# ControlBoard-v1_0.net
KiCad netlist of a schematic drawn in EAGLE
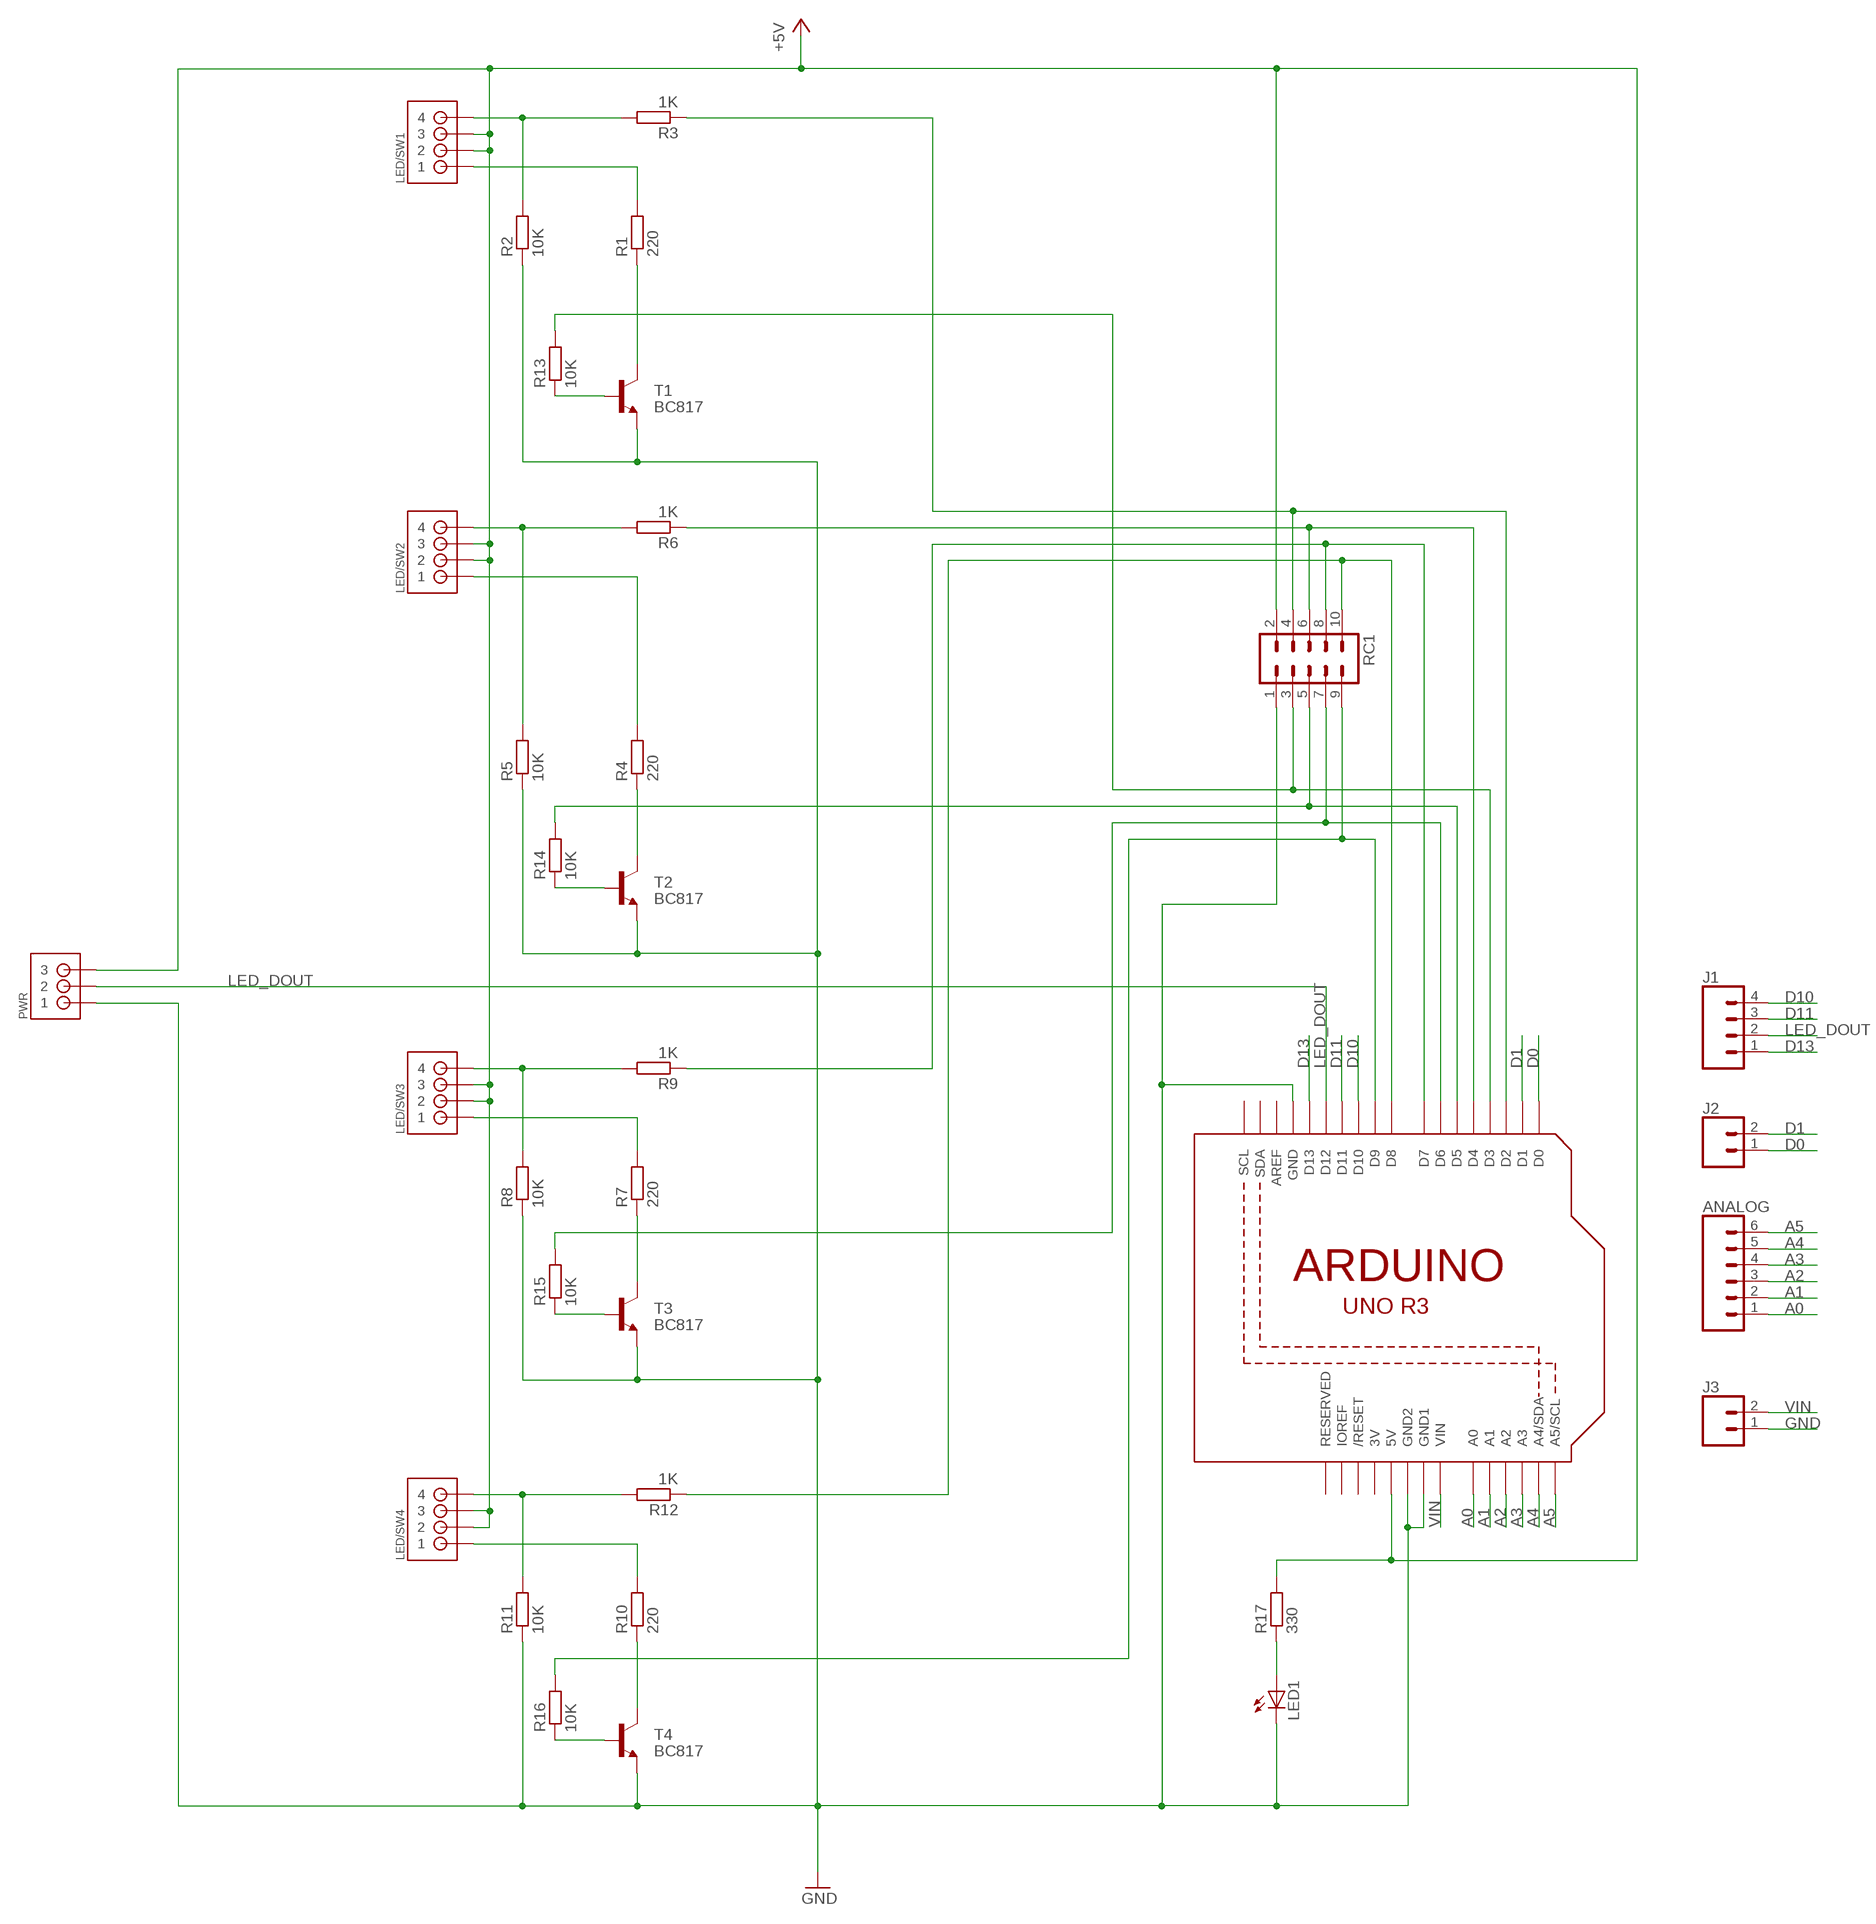
[diagram p0: schematic, sheet 1]

(export (version "E")
  (design (tool "Eeschema 10.0.6"))
  (components
    (comp (ref "ANALOG")
      (value "CONN_06SILK_FEMALE_PTH")
      (footprint "eagle-import:1X06")
      (libsource (lib "eagle-import") (part "CONN_06SILK_FEMALE_PTH"))
    )
    (comp (ref "J1")
      (value "CONN_04")
      (footprint "eagle-import:1X04")
      (libsource (lib "eagle-import") (part "CONN_04"))
    )
    (comp (ref "J2")
      (value "CONN_02")
      (footprint "eagle-import:1X02")
      (libsource (lib "eagle-import") (part "CONN_02"))
    )
    (comp (ref "J3")
      (value "CONN_02")
      (footprint "eagle-import:1X02")
      (libsource (lib "eagle-import") (part "CONN_02"))
    )
    (comp (ref "LED/SW1")
      (value "JST-XA-04-PIN")
      (footprint "eagle-import:JST-XA-04")
      (libsource (lib "eagle-import") (part "JST-XA-04-PIN"))
    )
    (comp (ref "LED/SW2")
      (value "JST-XA-04-PIN")
      (footprint "eagle-import:JST-XA-04")
      (libsource (lib "eagle-import") (part "JST-XA-04-PIN"))
    )
    (comp (ref "LED/SW3")
      (value "JST-XA-04-PIN")
      (footprint "eagle-import:JST-XA-04")
      (libsource (lib "eagle-import") (part "JST-XA-04-PIN"))
    )
    (comp (ref "LED/SW4")
      (value "JST-XA-04-PIN")
      (footprint "eagle-import:JST-XA-04")
      (libsource (lib "eagle-import") (part "JST-XA-04-PIN"))
    )
    (comp (ref "LED1")
      (value "LEDCHIPLED_0805")
      (footprint "eagle-import:CHIPLED_0805")
      (libsource (lib "eagle-import") (part "LEDCHIPLED_0805"))
    )
    (comp (ref "PWR")
      (value "JST-XA-03-PIN")
      (footprint "eagle-import:JST-XA-03")
      (libsource (lib "eagle-import") (part "JST-XA-03-PIN"))
    )
    (comp (ref "R1")
      (value "220")
      (footprint "eagle-import:R0805")
      (libsource (lib "eagle-import") (part "RESISTORR0805"))
    )
    (comp (ref "R2")
      (value "10K")
      (footprint "eagle-import:R0805")
      (libsource (lib "eagle-import") (part "RESISTORR0805"))
    )
    (comp (ref "R3")
      (value "1K")
      (footprint "eagle-import:R0805")
      (libsource (lib "eagle-import") (part "RESISTORR0805"))
    )
    (comp (ref "R4")
      (value "220")
      (footprint "eagle-import:R0805")
      (libsource (lib "eagle-import") (part "RESISTORR0805"))
    )
    (comp (ref "R5")
      (value "10K")
      (footprint "eagle-import:R0805")
      (libsource (lib "eagle-import") (part "RESISTORR0805"))
    )
    (comp (ref "R6")
      (value "1K")
      (footprint "eagle-import:R0805")
      (libsource (lib "eagle-import") (part "RESISTORR0805"))
    )
    (comp (ref "R7")
      (value "220")
      (footprint "eagle-import:R0805")
      (libsource (lib "eagle-import") (part "RESISTORR0805"))
    )
    (comp (ref "R8")
      (value "10K")
      (footprint "eagle-import:R0805")
      (libsource (lib "eagle-import") (part "RESISTORR0805"))
    )
    (comp (ref "R9")
      (value "1K")
      (footprint "eagle-import:R0805")
      (libsource (lib "eagle-import") (part "RESISTORR0805"))
    )
    (comp (ref "R10")
      (value "220")
      (footprint "eagle-import:R0805")
      (libsource (lib "eagle-import") (part "RESISTORR0805"))
    )
    (comp (ref "R11")
      (value "10K")
      (footprint "eagle-import:R0805")
      (libsource (lib "eagle-import") (part "RESISTORR0805"))
    )
    (comp (ref "R12")
      (value "1K")
      (footprint "eagle-import:R0805")
      (libsource (lib "eagle-import") (part "RESISTORR0805"))
    )
    (comp (ref "R13")
      (value "10K")
      (footprint "eagle-import:R0805")
      (libsource (lib "eagle-import") (part "RESISTORR0805"))
    )
    (comp (ref "R14")
      (value "10K")
      (footprint "eagle-import:R0805")
      (libsource (lib "eagle-import") (part "RESISTORR0805"))
    )
    (comp (ref "R15")
      (value "10K")
      (footprint "eagle-import:R0805")
      (libsource (lib "eagle-import") (part "RESISTORR0805"))
    )
    (comp (ref "R16")
      (value "10K")
      (footprint "eagle-import:R0805")
      (libsource (lib "eagle-import") (part "RESISTORR0805"))
    )
    (comp (ref "R17")
      (value "330")
      (footprint "eagle-import:R0805")
      (libsource (lib "eagle-import") (part "RESISTORR0805"))
    )
    (comp (ref "RC1")
      (value "ML10")
      (footprint "eagle-import:ML10")
      (libsource (lib "eagle-import") (part "ML10"))
    )
    (comp (ref "T1")
      (value "BC817")
      (footprint "eagle-import:SOT23")
      (libsource (lib "eagle-import") (part "BC817"))
    )
    (comp (ref "T2")
      (value "BC817")
      (footprint "eagle-import:SOT23")
      (libsource (lib "eagle-import") (part "BC817"))
    )
    (comp (ref "T3")
      (value "BC817")
      (footprint "eagle-import:SOT23")
      (libsource (lib "eagle-import") (part "BC817"))
    )
    (comp (ref "T4")
      (value "BC817")
      (footprint "eagle-import:SOT23")
      (libsource (lib "eagle-import") (part "BC817"))
    )
    (comp (ref "U1")
      (value "ARDUINO-SHIELDLET")
      (footprint "eagle-import:ARDUINOR3-PINS")
      (libsource (lib "eagle-import") (part "ARDUINO-SHIELDLET"))
    )
  )
  (nets
    (net (code "1") (name "+5V") (class "Default")
      (node (ref "LED/SW1") (pin "2") (pinfunction "2_2") (pintype "bidirectional"))
      (node (ref "LED/SW1") (pin "3") (pinfunction "3_3") (pintype "bidirectional"))
      (node (ref "LED/SW2") (pin "2") (pinfunction "2_2") (pintype "bidirectional"))
      (node (ref "LED/SW2") (pin "3") (pinfunction "3_3") (pintype "bidirectional"))
      (node (ref "LED/SW3") (pin "2") (pinfunction "2_2") (pintype "bidirectional"))
      (node (ref "LED/SW3") (pin "3") (pinfunction "3_3") (pintype "bidirectional"))
      (node (ref "LED/SW4") (pin "2") (pinfunction "2_2") (pintype "bidirectional"))
      (node (ref "LED/SW4") (pin "3") (pinfunction "3_3") (pintype "bidirectional"))
      (node (ref "PWR") (pin "3") (pinfunction "3_3") (pintype "bidirectional"))
      (node (ref "R17") (pin "2") (pinfunction "2_2") (pintype "passive"))
      (node (ref "RC1") (pin "2") (pinfunction "2_2") (pintype "passive"))
      (node (ref "U1") (pin "5V") (pinfunction "5V_5V") (pintype "power_in"))
    )
    (net (code "2") (name "/3V") (class "Default")
      (node (ref "U1") (pin "3V") (pinfunction "3V_3V") (pintype "power_in"))
    )
    (net (code "3") (name "/A0") (class "Default")
      (node (ref "ANALOG") (pin "1") (pinfunction "1_1") (pintype "passive"))
      (node (ref "U1") (pin "A0") (pinfunction "A0_A0") (pintype "bidirectional"))
    )
    (net (code "4") (name "/A1") (class "Default")
      (node (ref "ANALOG") (pin "2") (pinfunction "2_2") (pintype "passive"))
      (node (ref "U1") (pin "A1") (pinfunction "A1_A1") (pintype "bidirectional"))
    )
    (net (code "5") (name "/A2") (class "Default")
      (node (ref "ANALOG") (pin "3") (pinfunction "3_3") (pintype "passive"))
      (node (ref "U1") (pin "A2") (pinfunction "A2_A2") (pintype "bidirectional"))
    )
    (net (code "6") (name "/A3") (class "Default")
      (node (ref "ANALOG") (pin "4") (pinfunction "4_4") (pintype "passive"))
      (node (ref "U1") (pin "A3") (pinfunction "A3_A3") (pintype "bidirectional"))
    )
    (net (code "7") (name "/A4") (class "Default")
      (node (ref "ANALOG") (pin "5") (pinfunction "5_5") (pintype "passive"))
      (node (ref "U1") (pin "A4") (pinfunction "A4/SDA_A4") (pintype "bidirectional"))
    )
    (net (code "8") (name "/A5") (class "Default")
      (node (ref "ANALOG") (pin "6") (pinfunction "6_6") (pintype "passive"))
      (node (ref "U1") (pin "A5") (pinfunction "A5/SCL_A5") (pintype "bidirectional"))
    )
    (net (code "9") (name "/D0") (class "Default")
      (node (ref "J2") (pin "1") (pinfunction "1_1") (pintype "passive"))
      (node (ref "U1") (pin "D0") (pinfunction "D0_D0") (pintype "bidirectional"))
    )
    (net (code "10") (name "/D1") (class "Default")
      (node (ref "J2") (pin "2") (pinfunction "2_2") (pintype "passive"))
      (node (ref "U1") (pin "D1") (pinfunction "D1_D1") (pintype "bidirectional"))
    )
    (net (code "11") (name "/D10") (class "Default")
      (node (ref "J1") (pin "4") (pinfunction "4_4") (pintype "passive"))
      (node (ref "U1") (pin "D10") (pinfunction "D10_D10") (pintype "bidirectional"))
    )
    (net (code "12") (name "/D11") (class "Default")
      (node (ref "J1") (pin "3") (pinfunction "3_3") (pintype "passive"))
      (node (ref "U1") (pin "D11") (pinfunction "D11_D11") (pintype "bidirectional"))
    )
    (net (code "13") (name "/D13") (class "Default")
      (node (ref "J1") (pin "1") (pinfunction "1_1") (pintype "passive"))
      (node (ref "U1") (pin "D13") (pinfunction "D13_D13") (pintype "bidirectional"))
    )
    (net (code "14") (name "/LED_DOUT") (class "Default")
      (node (ref "J1") (pin "2") (pinfunction "2_2") (pintype "passive"))
      (node (ref "PWR") (pin "2") (pinfunction "2_2") (pintype "bidirectional"))
      (node (ref "U1") (pin "D12") (pinfunction "D12_D12") (pintype "bidirectional"))
    )
    (net (code "15") (name "/VIN") (class "Default")
      (node (ref "J3") (pin "2") (pinfunction "2_2") (pintype "passive"))
      (node (ref "U1") (pin "VIN") (pinfunction "VIN_VIN") (pintype "power_in"))
    )
    (net (code "16") (name "GND") (class "Default")
      (node (ref "J3") (pin "1") (pinfunction "1_1") (pintype "passive"))
      (node (ref "LED1") (pin "C") (pinfunction "C_C") (pintype "passive"))
      (node (ref "PWR") (pin "1") (pinfunction "1_1") (pintype "bidirectional"))
      (node (ref "R11") (pin "1") (pinfunction "1_1") (pintype "passive"))
      (node (ref "R2") (pin "1") (pinfunction "1_1") (pintype "passive"))
      (node (ref "R5") (pin "1") (pinfunction "1_1") (pintype "passive"))
      (node (ref "R8") (pin "1") (pinfunction "1_1") (pintype "passive"))
      (node (ref "RC1") (pin "1") (pinfunction "1_1") (pintype "passive"))
      (node (ref "T1") (pin "2") (pinfunction "E_2") (pintype "passive"))
      (node (ref "T2") (pin "2") (pinfunction "E_2") (pintype "passive"))
      (node (ref "T3") (pin "2") (pinfunction "E_2") (pintype "passive"))
      (node (ref "T4") (pin "2") (pinfunction "E_2") (pintype "passive"))
      (node (ref "U1") (pin "GND") (pinfunction "GND_GND") (pintype "power_in"))
      (node (ref "U1") (pin "GND1") (pinfunction "GND1_GND1") (pintype "power_in"))
      (node (ref "U1") (pin "GND2") (pinfunction "GND2_GND2") (pintype "power_in"))
    )
    (net (code "17") (name "Net-(LED/SW1-Pad1)") (class "Default")
      (node (ref "LED/SW1") (pin "1") (pinfunction "1_1") (pintype "bidirectional"))
      (node (ref "R1") (pin "2") (pinfunction "2_2") (pintype "passive"))
    )
    (net (code "18") (name "Net-(LED/SW1-Pad4)") (class "Default")
      (node (ref "LED/SW1") (pin "4") (pinfunction "4_4") (pintype "bidirectional"))
      (node (ref "R2") (pin "2") (pinfunction "2_2") (pintype "passive"))
      (node (ref "R3") (pin "2") (pinfunction "2_2") (pintype "passive"))
    )
    (net (code "19") (name "Net-(LED/SW2-Pad1)") (class "Default")
      (node (ref "LED/SW2") (pin "1") (pinfunction "1_1") (pintype "bidirectional"))
      (node (ref "R4") (pin "2") (pinfunction "2_2") (pintype "passive"))
    )
    (net (code "20") (name "Net-(LED/SW2-Pad4)") (class "Default")
      (node (ref "LED/SW2") (pin "4") (pinfunction "4_4") (pintype "bidirectional"))
      (node (ref "R5") (pin "2") (pinfunction "2_2") (pintype "passive"))
      (node (ref "R6") (pin "2") (pinfunction "2_2") (pintype "passive"))
    )
    (net (code "21") (name "Net-(LED/SW3-Pad1)") (class "Default")
      (node (ref "LED/SW3") (pin "1") (pinfunction "1_1") (pintype "bidirectional"))
      (node (ref "R7") (pin "2") (pinfunction "2_2") (pintype "passive"))
    )
    (net (code "22") (name "Net-(LED/SW3-Pad4)") (class "Default")
      (node (ref "LED/SW3") (pin "4") (pinfunction "4_4") (pintype "bidirectional"))
      (node (ref "R8") (pin "2") (pinfunction "2_2") (pintype "passive"))
      (node (ref "R9") (pin "2") (pinfunction "2_2") (pintype "passive"))
    )
    (net (code "23") (name "Net-(LED/SW4-Pad1)") (class "Default")
      (node (ref "LED/SW4") (pin "1") (pinfunction "1_1") (pintype "bidirectional"))
      (node (ref "R10") (pin "2") (pinfunction "2_2") (pintype "passive"))
    )
    (net (code "24") (name "Net-(LED/SW4-Pad4)") (class "Default")
      (node (ref "LED/SW4") (pin "4") (pinfunction "4_4") (pintype "bidirectional"))
      (node (ref "R11") (pin "2") (pinfunction "2_2") (pintype "passive"))
      (node (ref "R12") (pin "2") (pinfunction "2_2") (pintype "passive"))
    )
    (net (code "25") (name "Net-(LED1-PadA)") (class "Default")
      (node (ref "LED1") (pin "A") (pinfunction "A_A") (pintype "passive"))
      (node (ref "R17") (pin "1") (pinfunction "1_1") (pintype "passive"))
    )
    (net (code "26") (name "Net-(R3-Pad1)") (class "Default")
      (node (ref "R3") (pin "1") (pinfunction "1_1") (pintype "passive"))
      (node (ref "RC1") (pin "4") (pinfunction "4_4") (pintype "passive"))
      (node (ref "U1") (pin "D2") (pinfunction "D2_D2") (pintype "bidirectional"))
    )
    (net (code "27") (name "Net-(R6-Pad1)") (class "Default")
      (node (ref "R6") (pin "1") (pinfunction "1_1") (pintype "passive"))
      (node (ref "RC1") (pin "6") (pinfunction "6_6") (pintype "passive"))
      (node (ref "U1") (pin "D4") (pinfunction "D4_D4") (pintype "bidirectional"))
    )
    (net (code "28") (name "Net-(R9-Pad1)") (class "Default")
      (node (ref "R9") (pin "1") (pinfunction "1_1") (pintype "passive"))
      (node (ref "RC1") (pin "8") (pinfunction "8_8") (pintype "passive"))
      (node (ref "U1") (pin "D7") (pinfunction "D7_D7") (pintype "bidirectional"))
    )
    (net (code "29") (name "Net-(R12-Pad1)") (class "Default")
      (node (ref "R12") (pin "1") (pinfunction "1_1") (pintype "passive"))
      (node (ref "RC1") (pin "10") (pinfunction "10_10") (pintype "passive"))
      (node (ref "U1") (pin "D8") (pinfunction "D8_D8") (pintype "bidirectional"))
    )
    (net (code "30") (name "Net-(R13-Pad2)") (class "Default")
      (node (ref "R13") (pin "2") (pinfunction "2_2") (pintype "passive"))
      (node (ref "RC1") (pin "3") (pinfunction "3_3") (pintype "passive"))
      (node (ref "U1") (pin "D3") (pinfunction "D3_D3") (pintype "bidirectional"))
    )
    (net (code "31") (name "Net-(R14-Pad2)") (class "Default")
      (node (ref "R14") (pin "2") (pinfunction "2_2") (pintype "passive"))
      (node (ref "RC1") (pin "5") (pinfunction "5_5") (pintype "passive"))
      (node (ref "U1") (pin "D5") (pinfunction "D5_D5") (pintype "bidirectional"))
    )
    (net (code "32") (name "Net-(R15-Pad2)") (class "Default")
      (node (ref "R15") (pin "2") (pinfunction "2_2") (pintype "passive"))
      (node (ref "RC1") (pin "7") (pinfunction "7_7") (pintype "passive"))
      (node (ref "U1") (pin "D6") (pinfunction "D6_D6") (pintype "bidirectional"))
    )
    (net (code "33") (name "Net-(R16-Pad2)") (class "Default")
      (node (ref "R16") (pin "2") (pinfunction "2_2") (pintype "passive"))
      (node (ref "RC1") (pin "9") (pinfunction "9_9") (pintype "passive"))
      (node (ref "U1") (pin "D9") (pinfunction "D9_D9") (pintype "bidirectional"))
    )
    (net (code "34") (name "Net-(T1-B)") (class "Default")
      (node (ref "R13") (pin "1") (pinfunction "1_1") (pintype "passive"))
      (node (ref "T1") (pin "1") (pinfunction "B_1") (pintype "passive"))
    )
    (net (code "35") (name "Net-(T1-C)") (class "Default")
      (node (ref "R1") (pin "1") (pinfunction "1_1") (pintype "passive"))
      (node (ref "T1") (pin "3") (pinfunction "C_3") (pintype "passive"))
    )
    (net (code "36") (name "Net-(T2-B)") (class "Default")
      (node (ref "R14") (pin "1") (pinfunction "1_1") (pintype "passive"))
      (node (ref "T2") (pin "1") (pinfunction "B_1") (pintype "passive"))
    )
    (net (code "37") (name "Net-(T2-C)") (class "Default")
      (node (ref "R4") (pin "1") (pinfunction "1_1") (pintype "passive"))
      (node (ref "T2") (pin "3") (pinfunction "C_3") (pintype "passive"))
    )
    (net (code "38") (name "Net-(T3-B)") (class "Default")
      (node (ref "R15") (pin "1") (pinfunction "1_1") (pintype "passive"))
      (node (ref "T3") (pin "1") (pinfunction "B_1") (pintype "passive"))
    )
    (net (code "39") (name "Net-(T3-C)") (class "Default")
      (node (ref "R7") (pin "1") (pinfunction "1_1") (pintype "passive"))
      (node (ref "T3") (pin "3") (pinfunction "C_3") (pintype "passive"))
    )
    (net (code "40") (name "Net-(T4-B)") (class "Default")
      (node (ref "R16") (pin "1") (pinfunction "1_1") (pintype "passive"))
      (node (ref "T4") (pin "1") (pinfunction "B_1") (pintype "passive"))
    )
    (net (code "41") (name "Net-(T4-C)") (class "Default")
      (node (ref "R10") (pin "1") (pinfunction "1_1") (pintype "passive"))
      (node (ref "T4") (pin "3") (pinfunction "C_3") (pintype "passive"))
    )
    (net (code "42") (name "unconnected-(U1-PadAREF)") (class "Default")
      (node (ref "U1") (pin "AREF") (pinfunction "AREF_AREF") (pintype "bidirectional"))
    )
    (net (code "43") (name "unconnected-(U1-PadIOREF)") (class "Default")
      (node (ref "U1") (pin "IOREF") (pinfunction "IOREF_IOREF") (pintype "output"))
    )
    (net (code "44") (name "unconnected-(U1-PadRESERVED)") (class "Default")
      (node (ref "U1") (pin "RESERVED") (pinfunction "RESERVED_RESERVED") (pintype "no_connect"))
    )
    (net (code "45") (name "unconnected-(U1-PadSCL)") (class "Default")
      (node (ref "U1") (pin "SCL") (pinfunction "SCL_SCL") (pintype "bidirectional"))
    )
    (net (code "46") (name "unconnected-(U1-PadSDA)") (class "Default")
      (node (ref "U1") (pin "SDA") (pinfunction "SDA_SDA") (pintype "bidirectional"))
    )
    (net (code "47") (name "unconnected-(U1-{slash}RESET-PadRESET)") (class "Default")
      (node (ref "U1") (pin "RESET") (pinfunction "/RESET_RESET") (pintype "bidirectional"))
    )
  )
)
